# WS2812B-B.net
KiCad netlist of a schematic drawn in Altium Designer
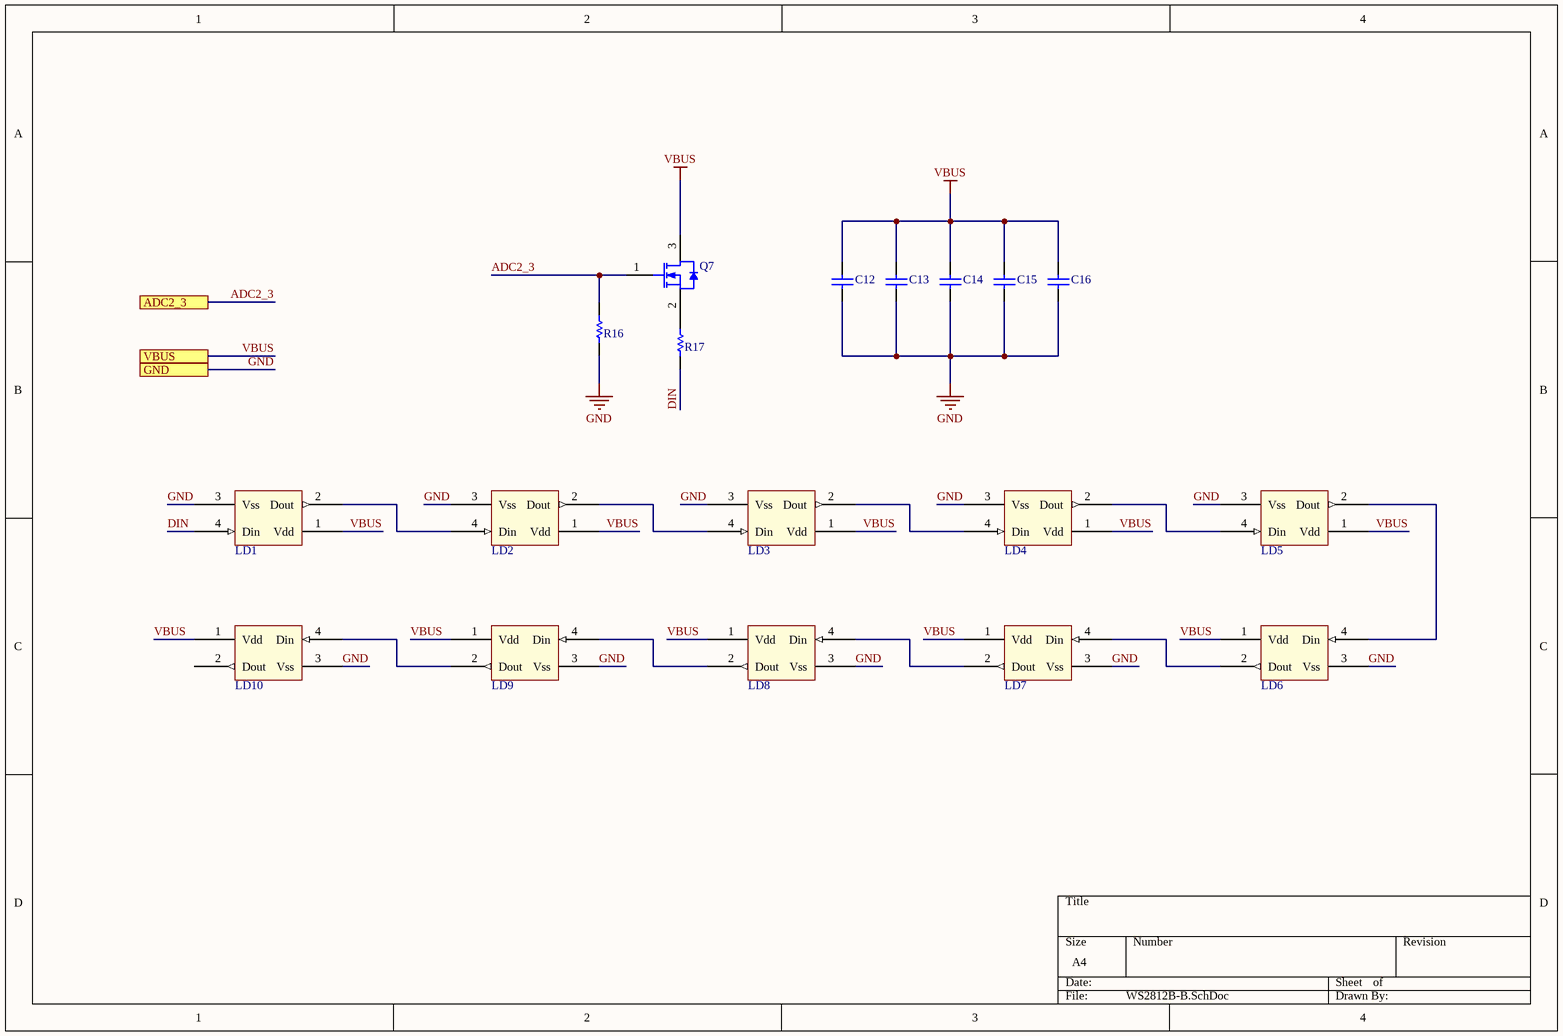
[diagram p0: WS2812B-B.SchDoc]

(export (version "E")
  (design (tool "Eeschema 10.0.6"))
  (components
    (comp (ref "C12")
      (value "C0805C105K4RAC7800")
      (footprint "CAPC2013X145X50NL20T25")
      (description "1µF ±10% 16V Ceramic Capacitor X7R 0805 (2012 Metric)")
      (fields (field (name "MANUFACTURER") "Kemet"))
      (libsource (lib "Altium Content Vault") (part "CAP"))
    )
    (comp (ref "C13")
      (value "C0805C105K4RAC7800")
      (footprint "CAPC2013X145X50NL20T25")
      (description "1µF ±10% 16V Ceramic Capacitor X7R 0805 (2012 Metric)")
      (fields (field (name "MANUFACTURER") "Kemet"))
      (libsource (lib "Altium Content Vault") (part "CAP"))
    )
    (comp (ref "C14")
      (value "C0805C105K4RAC7800")
      (footprint "CAPC2013X145X50NL20T25")
      (description "1µF ±10% 16V Ceramic Capacitor X7R 0805 (2012 Metric)")
      (fields (field (name "MANUFACTURER") "Kemet"))
      (libsource (lib "Altium Content Vault") (part "CAP"))
    )
    (comp (ref "C15")
      (value "C0805C105K4RAC7800")
      (footprint "CAPC2013X145X50NL20T25")
      (description "1µF ±10% 16V Ceramic Capacitor X7R 0805 (2012 Metric)")
      (fields (field (name "MANUFACTURER") "Kemet"))
      (libsource (lib "Altium Content Vault") (part "CAP"))
    )
    (comp (ref "C16")
      (value "C0805C105K4RAC7800")
      (footprint "CAPC2013X145X50NL20T25")
      (description "1µF ±10% 16V Ceramic Capacitor X7R 0805 (2012 Metric)")
      (fields (field (name "MANUFACTURER") "Kemet"))
      (libsource (lib "Altium Content Vault") (part "CAP"))
    )
    (comp (ref "LD1")
      (value "WS2812B-B")
      (footprint "WS2812B")
      (description "Neopixel Led 5050- ws2812b RGB")
      (libsource (lib "LIB_FIT") (part "WS2812B"))
    )
    (comp (ref "LD2")
      (value "WS2812B-B")
      (footprint "WS2812B")
      (description "Neopixel Led 5050- ws2812b RGB")
      (libsource (lib "LIB_FIT") (part "WS2812B"))
    )
    (comp (ref "LD3")
      (value "WS2812B-B")
      (footprint "WS2812B")
      (description "Neopixel Led 5050- ws2812b RGB")
      (libsource (lib "LIB_FIT") (part "WS2812B"))
    )
    (comp (ref "LD4")
      (value "WS2812B-B")
      (footprint "WS2812B")
      (description "Neopixel Led 5050- ws2812b RGB")
      (libsource (lib "LIB_FIT") (part "WS2812B"))
    )
    (comp (ref "LD5")
      (value "WS2812B-B")
      (footprint "WS2812B")
      (description "Neopixel Led 5050- ws2812b RGB")
      (libsource (lib "LIB_FIT") (part "WS2812B"))
    )
    (comp (ref "LD6")
      (value "WS2812B-B")
      (footprint "WS2812B")
      (description "Neopixel Led 5050- ws2812b RGB")
      (libsource (lib "") (part "WS2812B_1"))
    )
    (comp (ref "LD7")
      (value "WS2812B-B")
      (footprint "WS2812B")
      (description "Neopixel Led 5050- ws2812b RGB")
      (libsource (lib "") (part "WS2812B_1"))
    )
    (comp (ref "LD8")
      (value "WS2812B-B")
      (footprint "WS2812B")
      (description "Neopixel Led 5050- ws2812b RGB")
      (libsource (lib "") (part "WS2812B_1"))
    )
    (comp (ref "LD9")
      (value "WS2812B-B")
      (footprint "WS2812B")
      (description "Neopixel Led 5050- ws2812b RGB")
      (libsource (lib "") (part "WS2812B_1"))
    )
    (comp (ref "LD10")
      (value "WS2812B-B")
      (footprint "WS2812B")
      (description "Neopixel Led 5050- ws2812b RGB")
      (libsource (lib "") (part "WS2812B_1"))
    )
    (comp (ref "Q7")
      (value "BSS138-7-F")
      (footprint "DIOD-SOT23-3_V")
      (description "N-Channel Enhancement Mode Mosfet, 50 V, 0.2 A, -55 to 150 degC, 3-Pin SOT23, RoHS, Tape and Reel")
      (fields (field (name "MANUFACTURER") "Diodes Inc"))
      (libsource (lib "Altium Content Vault") (part "NEMOS-GSD-3"))
    )
    (comp (ref "R16")
      (value "RK73B2ATTD103J")
      (footprint "RESC2013X60X30NL20T20")
      (fields (field (name "MANUFACTURER") "KOA Speer"))
      (libsource (lib "Altium Content Vault") (part "RES"))
    )
    (comp (ref "R17")
      (value "RK73B2ATTD471J")
      (footprint "RESC2013X60X30NL20T20")
      (fields (field (name "MANUFACTURER") "KOA Speer"))
      (libsource (lib "Altium Content Vault") (part "RES"))
    )
  )
  (nets
    (net (code "1") (name "/ADC2_3") (class "Default")
      (node (ref "Q7") (pin "1") (pinfunction "G_1") (pintype "passive"))
      (node (ref "R16") (pin "1") (pinfunction "1_1") (pintype "passive"))
    )
    (net (code "2") (name "/DIN") (class "Default")
      (node (ref "LD1") (pin "4") (pinfunction "Din_4") (pintype "input"))
      (node (ref "R17") (pin "1") (pinfunction "1_1") (pintype "passive"))
    )
    (net (code "3") (name "GND") (class "Default")
      (node (ref "C12") (pin "1") (pinfunction "1_1") (pintype "passive"))
      (node (ref "C13") (pin "1") (pinfunction "1_1") (pintype "passive"))
      (node (ref "C14") (pin "1") (pinfunction "1_1") (pintype "passive"))
      (node (ref "C15") (pin "1") (pinfunction "1_1") (pintype "passive"))
      (node (ref "C16") (pin "1") (pinfunction "1_1") (pintype "passive"))
      (node (ref "LD1") (pin "3") (pinfunction "Vss_3") (pintype "power_in"))
      (node (ref "LD10") (pin "3") (pinfunction "Vss_3") (pintype "power_in"))
      (node (ref "LD2") (pin "3") (pinfunction "Vss_3") (pintype "power_in"))
      (node (ref "LD3") (pin "3") (pinfunction "Vss_3") (pintype "power_in"))
      (node (ref "LD4") (pin "3") (pinfunction "Vss_3") (pintype "power_in"))
      (node (ref "LD5") (pin "3") (pinfunction "Vss_3") (pintype "power_in"))
      (node (ref "LD6") (pin "3") (pinfunction "Vss_3") (pintype "power_in"))
      (node (ref "LD7") (pin "3") (pinfunction "Vss_3") (pintype "power_in"))
      (node (ref "LD8") (pin "3") (pinfunction "Vss_3") (pintype "power_in"))
      (node (ref "LD9") (pin "3") (pinfunction "Vss_3") (pintype "power_in"))
      (node (ref "R16") (pin "2") (pinfunction "2_2") (pintype "passive"))
    )
    (net (code "4") (name "Net-(LD1-Dout)") (class "Default")
      (node (ref "LD1") (pin "2") (pinfunction "Dout_2") (pintype "output"))
      (node (ref "LD2") (pin "4") (pinfunction "Din_4") (pintype "input"))
    )
    (net (code "5") (name "Net-(LD2-Dout)") (class "Default")
      (node (ref "LD2") (pin "2") (pinfunction "Dout_2") (pintype "output"))
      (node (ref "LD3") (pin "4") (pinfunction "Din_4") (pintype "input"))
    )
    (net (code "6") (name "Net-(LD3-Dout)") (class "Default")
      (node (ref "LD3") (pin "2") (pinfunction "Dout_2") (pintype "output"))
      (node (ref "LD4") (pin "4") (pinfunction "Din_4") (pintype "input"))
    )
    (net (code "7") (name "Net-(LD4-Dout)") (class "Default")
      (node (ref "LD4") (pin "2") (pinfunction "Dout_2") (pintype "output"))
      (node (ref "LD5") (pin "4") (pinfunction "Din_4") (pintype "input"))
    )
    (net (code "8") (name "Net-(LD5-Dout)") (class "Default")
      (node (ref "LD5") (pin "2") (pinfunction "Dout_2") (pintype "output"))
      (node (ref "LD6") (pin "4") (pinfunction "Din_4") (pintype "input"))
    )
    (net (code "9") (name "Net-(LD6-Dout)") (class "Default")
      (node (ref "LD6") (pin "2") (pinfunction "Dout_2") (pintype "output"))
      (node (ref "LD7") (pin "4") (pinfunction "Din_4") (pintype "input"))
    )
    (net (code "10") (name "Net-(LD7-Dout)") (class "Default")
      (node (ref "LD7") (pin "2") (pinfunction "Dout_2") (pintype "output"))
      (node (ref "LD8") (pin "4") (pinfunction "Din_4") (pintype "input"))
    )
    (net (code "11") (name "Net-(LD8-Dout)") (class "Default")
      (node (ref "LD8") (pin "2") (pinfunction "Dout_2") (pintype "output"))
      (node (ref "LD9") (pin "4") (pinfunction "Din_4") (pintype "input"))
    )
    (net (code "12") (name "Net-(LD10-Din)") (class "Default")
      (node (ref "LD10") (pin "4") (pinfunction "Din_4") (pintype "input"))
      (node (ref "LD9") (pin "2") (pinfunction "Dout_2") (pintype "output"))
    )
    (net (code "13") (name "Net-(Q7-S)") (class "Default")
      (node (ref "Q7") (pin "2") (pinfunction "S_2") (pintype "passive"))
      (node (ref "R17") (pin "2") (pinfunction "2_2") (pintype "passive"))
    )
    (net (code "14") (name "VBUS") (class "Default")
      (node (ref "C12") (pin "2") (pinfunction "2_2") (pintype "passive"))
      (node (ref "C13") (pin "2") (pinfunction "2_2") (pintype "passive"))
      (node (ref "C14") (pin "2") (pinfunction "2_2") (pintype "passive"))
      (node (ref "C15") (pin "2") (pinfunction "2_2") (pintype "passive"))
      (node (ref "C16") (pin "2") (pinfunction "2_2") (pintype "passive"))
      (node (ref "LD1") (pin "1") (pinfunction "Vdd_1") (pintype "power_in"))
      (node (ref "LD10") (pin "1") (pinfunction "Vdd_1") (pintype "power_in"))
      (node (ref "LD2") (pin "1") (pinfunction "Vdd_1") (pintype "power_in"))
      (node (ref "LD3") (pin "1") (pinfunction "Vdd_1") (pintype "power_in"))
      (node (ref "LD4") (pin "1") (pinfunction "Vdd_1") (pintype "power_in"))
      (node (ref "LD5") (pin "1") (pinfunction "Vdd_1") (pintype "power_in"))
      (node (ref "LD6") (pin "1") (pinfunction "Vdd_1") (pintype "power_in"))
      (node (ref "LD7") (pin "1") (pinfunction "Vdd_1") (pintype "power_in"))
      (node (ref "LD8") (pin "1") (pinfunction "Vdd_1") (pintype "power_in"))
      (node (ref "LD9") (pin "1") (pinfunction "Vdd_1") (pintype "power_in"))
      (node (ref "Q7") (pin "3") (pinfunction "D_3") (pintype "passive"))
    )
    (net (code "15") (name "unconnected-(LD10-Dout-Pad2)") (class "Default")
      (node (ref "LD10") (pin "2") (pinfunction "Dout_2") (pintype "output"))
    )
  )
)
